# schematic.net
KiCad netlist of a schematic drawn in EasyEDA
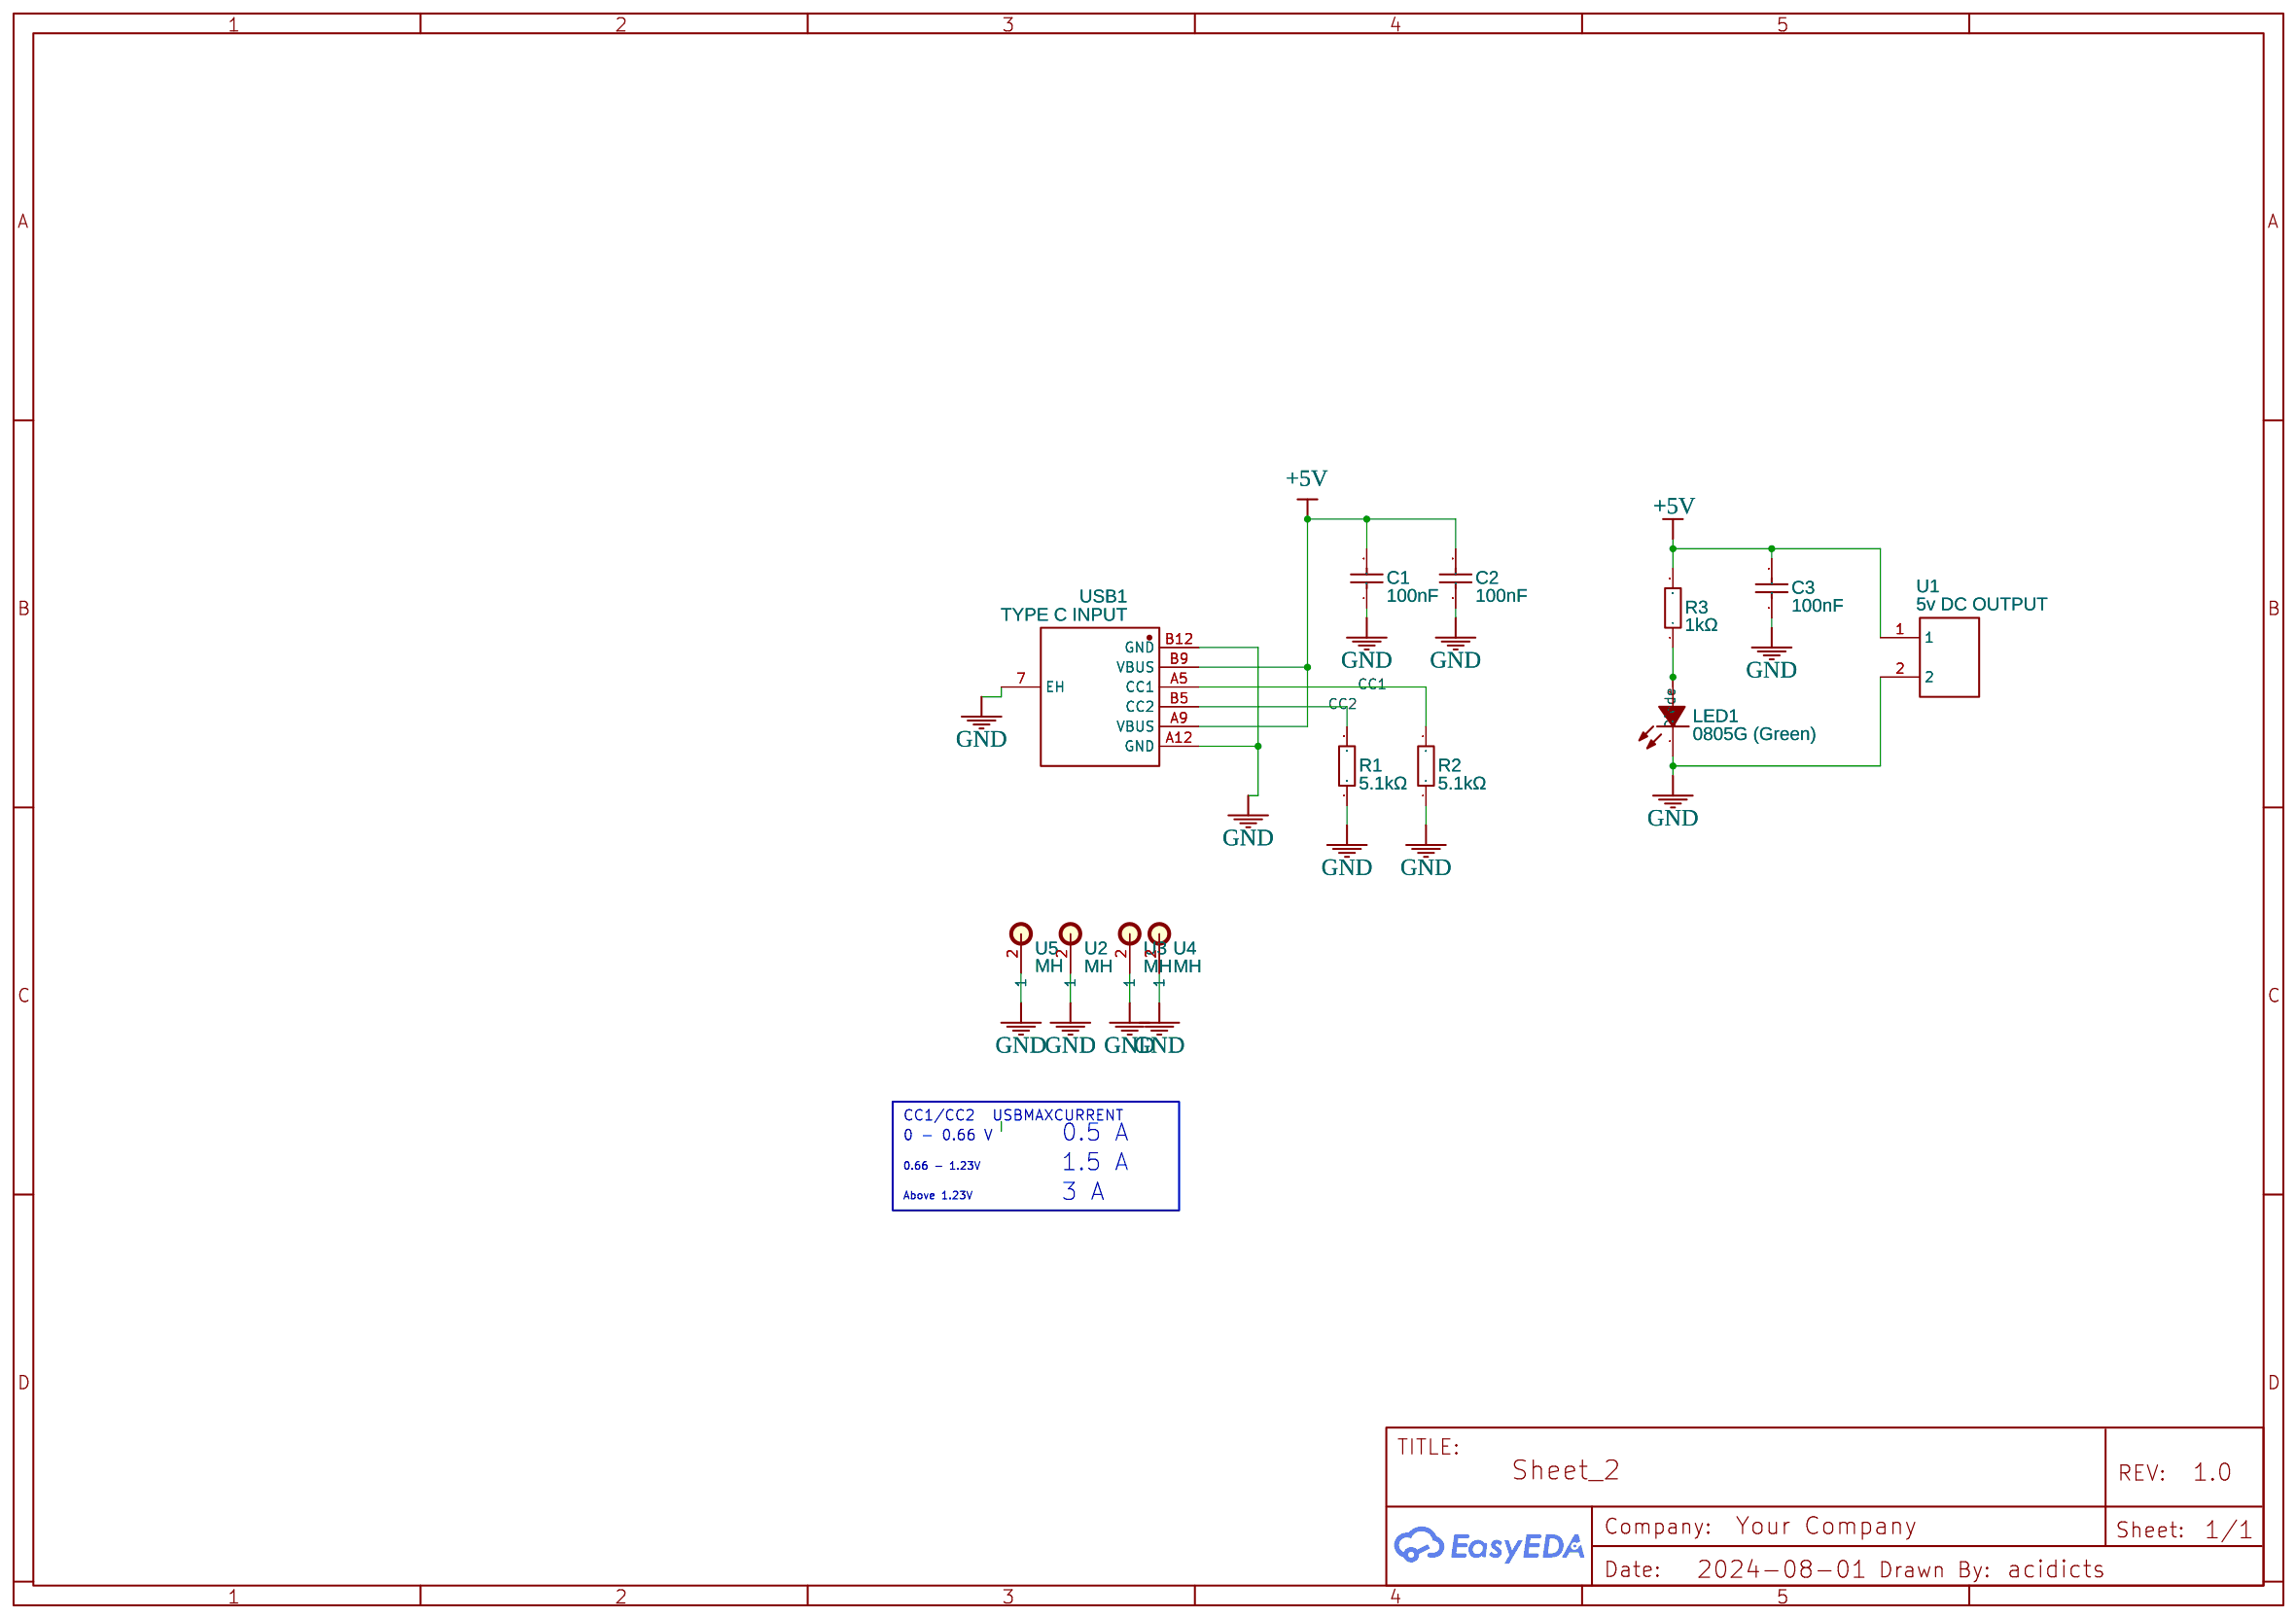
[diagram p0: schematic sheet]

(export (version "E")
  (design (tool "Eeschema 10.0.6"))
  (components
    (comp (ref "C1")
      (value "100nF")
      (fields
        (field (name "Manufacturer Part") "CL21B104KCFNNNE")
        (field (name "Manufacturer") "SAMSUNG(三星)")
      )
      (libsource (lib "") (part "CL21B104KCFNNNE"))
    )
    (comp (ref "C2")
      (value "100nF")
      (fields
        (field (name "Manufacturer Part") "CL21B104KCFNNNE")
        (field (name "Manufacturer") "SAMSUNG(三星)")
      )
      (libsource (lib "") (part "CL21B104KCFNNNE"))
    )
    (comp (ref "C3")
      (value "100nF")
      (fields
        (field (name "Manufacturer Part") "CL21B104KCFNNNE")
        (field (name "Manufacturer") "SAMSUNG(三星)")
      )
      (libsource (lib "") (part "CL21B104KCFNNNE"))
    )
    (comp (ref "LED1")
      (value "0805G (Green)")
      (fields (field (name "Manufacturer Part") "KT-0805G") (field (name "Manufacturer") "KENTO"))
      (libsource (lib "") (part "0805G (Green)"))
    )
    (comp (ref "R1")
      (value "5.1kΩ")
      (fields
        (field (name "Manufacturer Part") "0805W8F5101T5E")
        (field (name "Manufacturer") "UNI-ROYAL(厚声)")
      )
      (libsource (lib "") (part "0805W8F5101T5E"))
    )
    (comp (ref "R2")
      (value "5.1kΩ")
      (fields
        (field (name "Manufacturer Part") "0805W8F5101T5E")
        (field (name "Manufacturer") "UNI-ROYAL(厚声)")
      )
      (libsource (lib "") (part "0805W8F5101T5E"))
    )
    (comp (ref "R3")
      (value "1kΩ")
      (fields
        (field (name "Manufacturer Part") "0805W8F1001T5E")
        (field (name "Manufacturer") "UNI-ROYAL(厚声)")
      )
      (libsource (lib "") (part "0805W8F1001T5E"))
    )
    (comp (ref "U1")
      (value "5v DC OUTPUT")
      (fields
        (field (name "Manufacturer Part") "MKDSN 1,5/ 2-5,08")
        (field (name "Manufacturer") "Phoenix Contact(菲尼克斯)")
      )
      (libsource (lib "") (part "MKDSN 1,5/ 2-5,08"))
    )
    (comp (ref "U2") (value "MH") (libsource (lib "") (part "New_Symbol")))
    (comp (ref "U3") (value "MH") (libsource (lib "") (part "New_Symbol")))
    (comp (ref "U4") (value "MH") (libsource (lib "") (part "New_Symbol")))
    (comp (ref "U5") (value "MH") (libsource (lib "") (part "New_Symbol")))
    (comp (ref "USB1")
      (value "TYPE C INPUT")
      (fields
        (field (name "Manufacturer Part") "TYPE-C 6P(073)")
        (field (name "Manufacturer") "SHOU HAN(首韩)")
      )
      (libsource (lib "") (part "TYPE-C 6P(073)"))
    )
  )
  (nets
    (net (code "1") (name "+5V") (class "Default")
      (node (ref "C1") (pin "2") (pinfunction "2_2") (pintype "input"))
      (node (ref "C2") (pin "2") (pinfunction "2_2") (pintype "input"))
      (node (ref "C3") (pin "2") (pinfunction "2_2") (pintype "input"))
      (node (ref "R3") (pin "2") (pinfunction "2_2") (pintype "input"))
      (node (ref "U1") (pin "1") (pinfunction "1_1") (pintype "unspecified"))
      (node (ref "USB1") (pin "A9") (pinfunction "VBUS_A9") (pintype "unspecified"))
      (node (ref "USB1") (pin "B9") (pinfunction "VBUS_B9") (pintype "unspecified"))
    )
    (net (code "2") (name "/CC1") (class "Default")
      (node (ref "R2") (pin "2") (pinfunction "2_2") (pintype "input"))
      (node (ref "USB1") (pin "A5") (pinfunction "CC1_A5") (pintype "unspecified"))
    )
    (net (code "3") (name "/CC2") (class "Default")
      (node (ref "R1") (pin "2") (pinfunction "2_2") (pintype "input"))
      (node (ref "USB1") (pin "B5") (pinfunction "CC2_B5") (pintype "unspecified"))
    )
    (net (code "4") (name "/Diode") (class "Default")
      (node (ref "LED1") (pin "1") (pinfunction "A_1") (pintype "unspecified"))
      (node (ref "R3") (pin "1") (pinfunction "1_1") (pintype "input"))
    )
    (net (code "5") (name "GND") (class "Default")
      (node (ref "C1") (pin "1") (pinfunction "1_1") (pintype "input"))
      (node (ref "C2") (pin "1") (pinfunction "1_1") (pintype "input"))
      (node (ref "C3") (pin "1") (pinfunction "1_1") (pintype "input"))
      (node (ref "LED1") (pin "2") (pinfunction "K_2") (pintype "unspecified"))
      (node (ref "R1") (pin "1") (pinfunction "1_1") (pintype "input"))
      (node (ref "R2") (pin "1") (pinfunction "1_1") (pintype "input"))
      (node (ref "U1") (pin "2") (pinfunction "2_2") (pintype "unspecified"))
      (node (ref "U2") (pin "2") (pinfunction "1_2") (pintype "unspecified"))
      (node (ref "U3") (pin "2") (pinfunction "1_2") (pintype "unspecified"))
      (node (ref "U4") (pin "2") (pinfunction "1_2") (pintype "unspecified"))
      (node (ref "U5") (pin "2") (pinfunction "1_2") (pintype "unspecified"))
      (node (ref "USB1") (pin "7") (pinfunction "EH_7") (pintype "unspecified"))
      (node (ref "USB1") (pin "A12") (pinfunction "GND_A12") (pintype "unspecified"))
      (node (ref "USB1") (pin "B12") (pinfunction "GND_B12") (pintype "unspecified"))
    )
  )
)
